# ATS.net
KiCad netlist of a schematic drawn in EAGLE
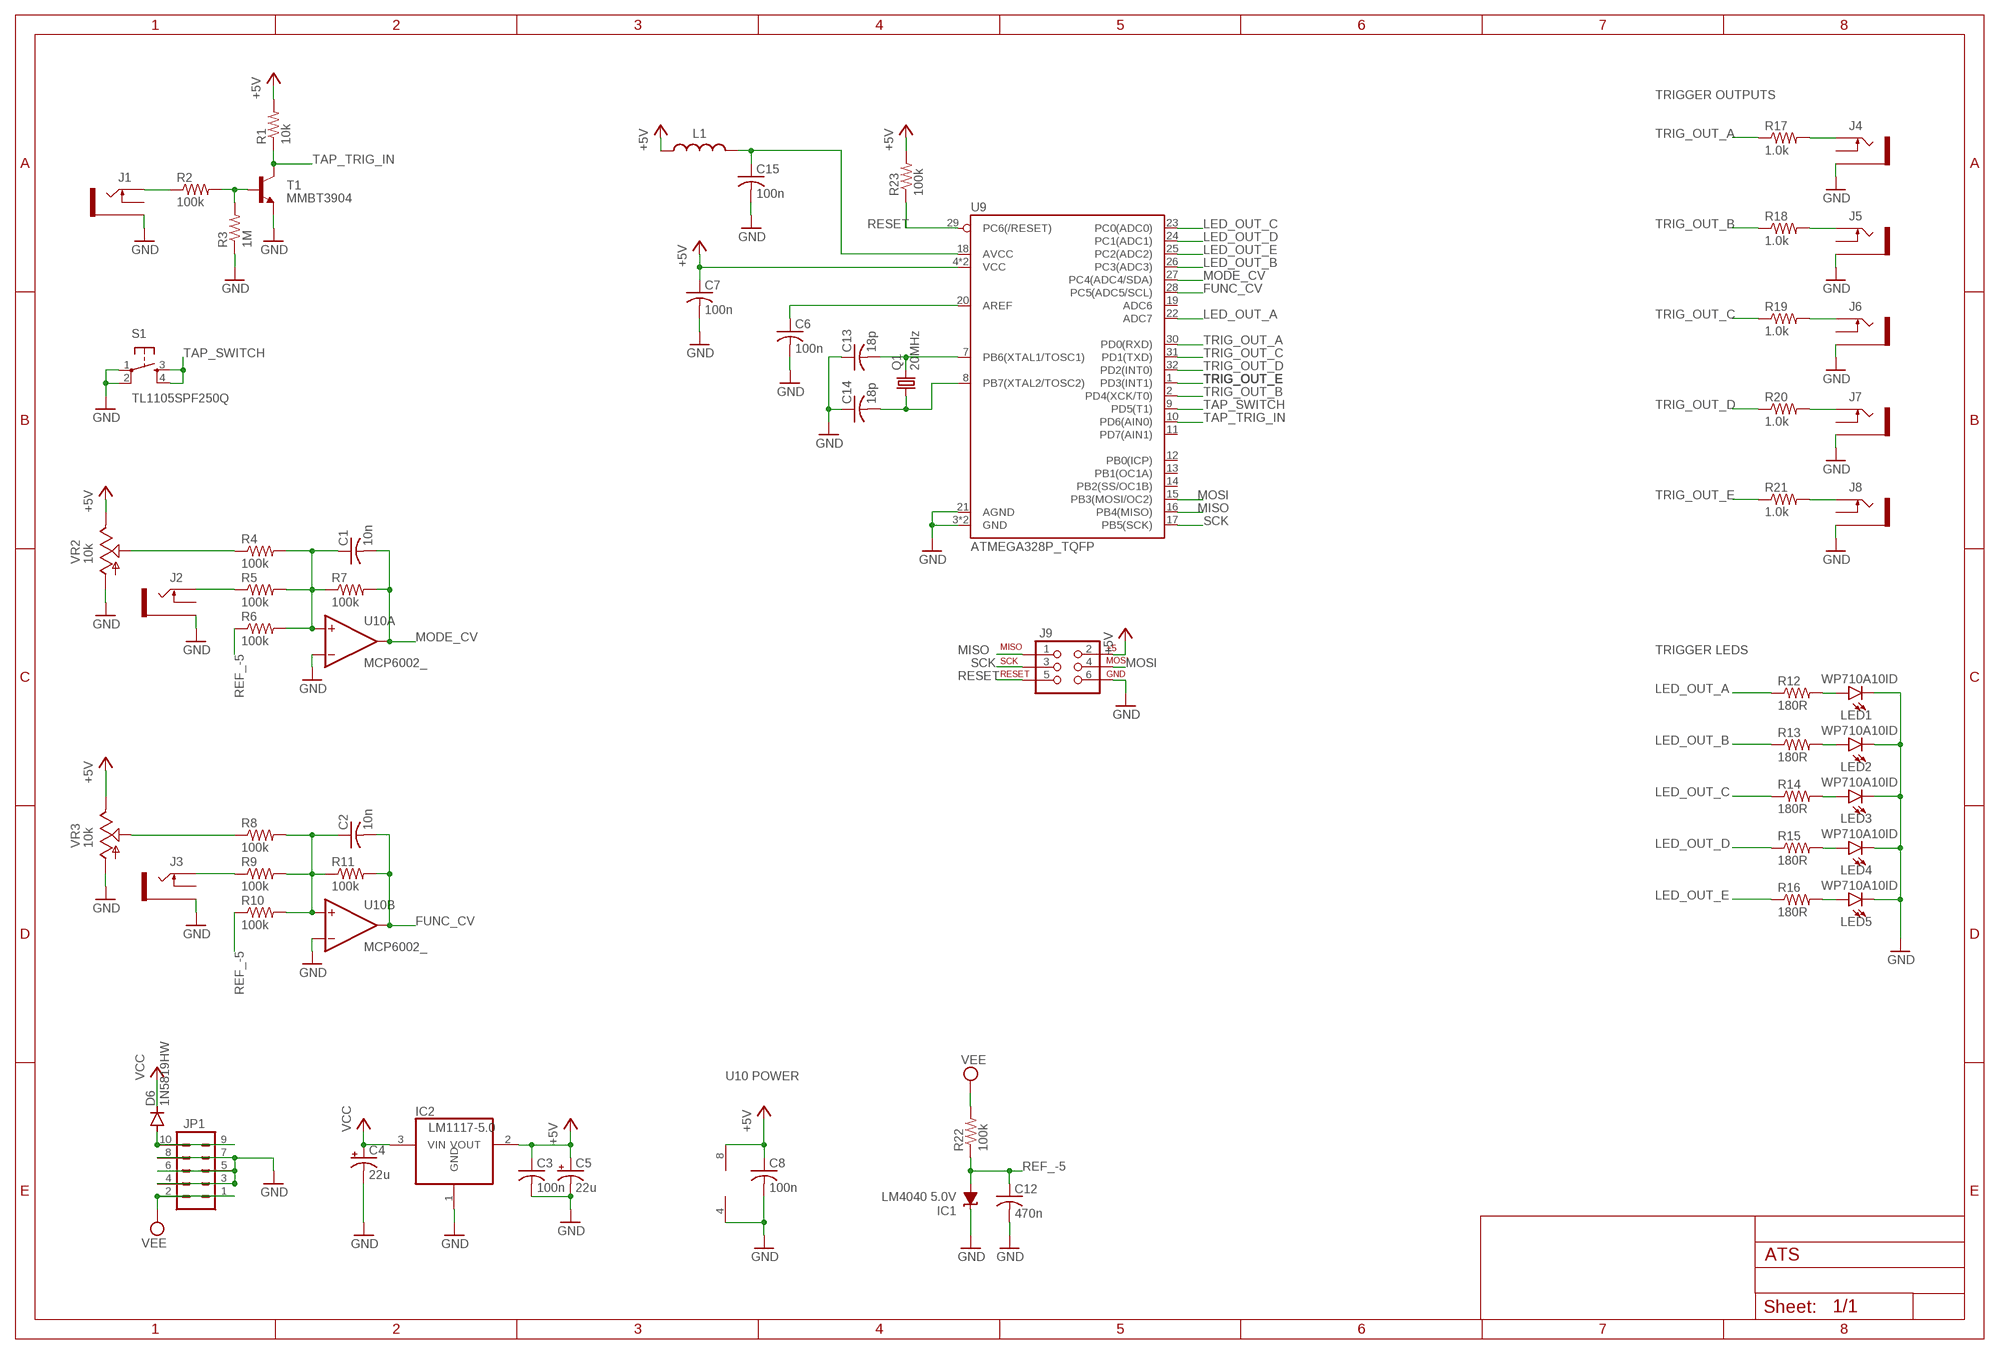
[diagram p0: schematic, sheet 1]

(export (version "E")
  (design (tool "Eeschema 10.0.6"))
  (components
    (comp (ref "C1")
      (value "10n")
      (footprint "eagle-import:C0603")
      (libsource (lib "eagle-import") (part "C-USC0603"))
    )
    (comp (ref "C2")
      (value "10n")
      (footprint "eagle-import:C0603")
      (libsource (lib "eagle-import") (part "C-USC0603"))
    )
    (comp (ref "C3")
      (value "100n")
      (footprint "eagle-import:C0603")
      (libsource (lib "eagle-import") (part "C-USC0603"))
    )
    (comp (ref "C4")
      (value "22u")
      (footprint "eagle-import:PANASONIC_C")
      (libsource (lib "eagle-import") (part "CPOL-USC"))
    )
    (comp (ref "C5")
      (value "22u")
      (footprint "eagle-import:PANASONIC_C")
      (libsource (lib "eagle-import") (part "CPOL-USC"))
    )
    (comp (ref "C6")
      (value "100n")
      (footprint "eagle-import:C0603")
      (libsource (lib "eagle-import") (part "C-USC0603"))
    )
    (comp (ref "C7")
      (value "100n")
      (footprint "eagle-import:C0603")
      (libsource (lib "eagle-import") (part "C-USC0603"))
    )
    (comp (ref "C8")
      (value "100n")
      (footprint "eagle-import:C0603")
      (libsource (lib "eagle-import") (part "C-USC0603"))
    )
    (comp (ref "C12")
      (value "470n")
      (footprint "eagle-import:C0603")
      (libsource (lib "eagle-import") (part "C-USC0603"))
    )
    (comp (ref "C13")
      (value "18p")
      (footprint "eagle-import:C0603")
      (libsource (lib "eagle-import") (part "C-USC0603"))
    )
    (comp (ref "C14")
      (value "18p")
      (footprint "eagle-import:C0603")
      (libsource (lib "eagle-import") (part "C-USC0603"))
    )
    (comp (ref "C15")
      (value "100n")
      (footprint "eagle-import:C0603")
      (libsource (lib "eagle-import") (part "C-USC0603"))
    )
    (comp (ref "D6")
      (value "1N5819HW")
      (footprint "eagle-import:SOD123")
      (libsource (lib "eagle-import") (part "DIODE-SOD123"))
    )
    (comp (ref "IC1")
      (value "LM4040 5.0V")
      (footprint "eagle-import:DBZ_R-PDSO-G3")
      (fields (field (name "MF") "TEXAS INSTRUMENT CONNECTORS") (field (name "MPN") "LM4041C12QDBZT"))
      (libsource (lib "eagle-import") (part "LM4041DBZC12"))
    )
    (comp (ref "IC2")
      (value "LM1117-5.0")
      (footprint "eagle-import:SOT223")
      (fields (field (name "MPN") "REG1117"))
      (libsource (lib "eagle-import") (part "REG1117"))
    )
    (comp (ref "J1")
      (value "THONKICONNNEW")
      (footprint "eagle-import:WQP-PJ301M-12_JACK")
      (libsource (lib "eagle-import") (part "THONKICONNNEW"))
    )
    (comp (ref "J2")
      (value "THONKICONNNEW")
      (footprint "eagle-import:WQP-PJ301M-12_JACK")
      (libsource (lib "eagle-import") (part "THONKICONNNEW"))
    )
    (comp (ref "J3")
      (value "THONKICONNNEW")
      (footprint "eagle-import:WQP-PJ301M-12_JACK")
      (libsource (lib "eagle-import") (part "THONKICONNNEW"))
    )
    (comp (ref "J4")
      (value "THONKICONNNEW")
      (footprint "eagle-import:WQP-PJ301M-12_JACK")
      (libsource (lib "eagle-import") (part "THONKICONNNEW"))
    )
    (comp (ref "J5")
      (value "THONKICONNNEW")
      (footprint "eagle-import:WQP-PJ301M-12_JACK")
      (libsource (lib "eagle-import") (part "THONKICONNNEW"))
    )
    (comp (ref "J6")
      (value "THONKICONNNEW")
      (footprint "eagle-import:WQP-PJ301M-12_JACK")
      (libsource (lib "eagle-import") (part "THONKICONNNEW"))
    )
    (comp (ref "J7")
      (value "THONKICONNNEW")
      (footprint "eagle-import:WQP-PJ301M-12_JACK")
      (libsource (lib "eagle-import") (part "THONKICONNNEW"))
    )
    (comp (ref "J8")
      (value "THONKICONNNEW")
      (footprint "eagle-import:WQP-PJ301M-12_JACK")
      (libsource (lib "eagle-import") (part "THONKICONNNEW"))
    )
    (comp (ref "J9")
      (value "AVR_SPI_PRG_6PTH")
      (footprint "eagle-import:2X3")
      (libsource (lib "eagle-import") (part "AVR_SPI_PRG_6PTH"))
    )
    (comp (ref "JP1")
      (value "EURO_POWER_HEADERREGULAR")
      (footprint "eagle-import:EURO_POWER_HEADER")
      (libsource (lib "eagle-import") (part "EURO_POWER_HEADERREGULAR"))
    )
    (comp (ref "L1")
      (value "470Ohm@100MHz")
      (footprint "eagle-import:WE-CBF_0603(W=2.2)")
      (libsource (lib "eagle-import") (part "WE-CBF_0603_WB_HS_742792642"))
    )
    (comp (ref "LED1")
      (value "WP710A10ID")
      (footprint "eagle-import:LED_3MM")
      (fields (field (name "SPICEPREFIX") "D"))
      (libsource (lib "eagle-import") (part "LED3MM"))
    )
    (comp (ref "LED2")
      (value "WP710A10ID")
      (footprint "eagle-import:LED_3MM")
      (libsource (lib "eagle-import") (part "LED3MM"))
    )
    (comp (ref "LED3")
      (value "WP710A10ID")
      (footprint "eagle-import:LED_3MM")
      (libsource (lib "eagle-import") (part "LED3MM"))
    )
    (comp (ref "LED4")
      (value "WP710A10ID")
      (footprint "eagle-import:LED_3MM")
      (libsource (lib "eagle-import") (part "LED3MM"))
    )
    (comp (ref "LED5")
      (value "WP710A10ID")
      (footprint "eagle-import:LED_3MM")
      (libsource (lib "eagle-import") (part "LED3MM"))
    )
    (comp (ref "Q1")
      (value "20MHz")
      (footprint "eagle-import:HC49UP")
      (libsource (lib "eagle-import") (part "CRYSTALHC49UP"))
    )
    (comp (ref "R1")
      (value "10k")
      (footprint "eagle-import:R0603")
      (libsource (lib "eagle-import") (part "R-US_R0603"))
    )
    (comp (ref "R2")
      (value "100k")
      (footprint "eagle-import:R0603")
      (libsource (lib "eagle-import") (part "R-US_R0603"))
    )
    (comp (ref "R3")
      (value "1M")
      (footprint "eagle-import:R0603")
      (libsource (lib "eagle-import") (part "R-US_R0603"))
    )
    (comp (ref "R4")
      (value "100k")
      (footprint "eagle-import:R0603")
      (libsource (lib "eagle-import") (part "R-US_R0603"))
    )
    (comp (ref "R5")
      (value "100k")
      (footprint "eagle-import:R0603")
      (libsource (lib "eagle-import") (part "R-US_R0603"))
    )
    (comp (ref "R6")
      (value "100k")
      (footprint "eagle-import:R0603")
      (libsource (lib "eagle-import") (part "R-US_R0603"))
    )
    (comp (ref "R7")
      (value "100k")
      (footprint "eagle-import:R0603")
      (libsource (lib "eagle-import") (part "R-US_R0603"))
    )
    (comp (ref "R8")
      (value "100k")
      (footprint "eagle-import:R0603")
      (libsource (lib "eagle-import") (part "R-US_R0603"))
    )
    (comp (ref "R9")
      (value "100k")
      (footprint "eagle-import:R0603")
      (libsource (lib "eagle-import") (part "R-US_R0603"))
    )
    (comp (ref "R10")
      (value "100k")
      (footprint "eagle-import:R0603")
      (libsource (lib "eagle-import") (part "R-US_R0603"))
    )
    (comp (ref "R11")
      (value "100k")
      (footprint "eagle-import:R0603")
      (libsource (lib "eagle-import") (part "R-US_R0603"))
    )
    (comp (ref "R12")
      (value "180R")
      (footprint "eagle-import:R0603")
      (libsource (lib "eagle-import") (part "R-US_R0603"))
    )
    (comp (ref "R13")
      (value "180R")
      (footprint "eagle-import:R0603")
      (libsource (lib "eagle-import") (part "R-US_R0603"))
    )
    (comp (ref "R14")
      (value "180R")
      (footprint "eagle-import:R0603")
      (libsource (lib "eagle-import") (part "R-US_R0603"))
    )
    (comp (ref "R15")
      (value "180R")
      (footprint "eagle-import:R0603")
      (libsource (lib "eagle-import") (part "R-US_R0603"))
    )
    (comp (ref "R16")
      (value "180R")
      (footprint "eagle-import:R0603")
      (libsource (lib "eagle-import") (part "R-US_R0603"))
    )
    (comp (ref "R17")
      (value "1.0k")
      (footprint "eagle-import:R0603")
      (libsource (lib "eagle-import") (part "R-US_R0603"))
    )
    (comp (ref "R18")
      (value "1.0k")
      (footprint "eagle-import:R0603")
      (libsource (lib "eagle-import") (part "R-US_R0603"))
    )
    (comp (ref "R19")
      (value "1.0k")
      (footprint "eagle-import:R0603")
      (libsource (lib "eagle-import") (part "R-US_R0603"))
    )
    (comp (ref "R20")
      (value "1.0k")
      (footprint "eagle-import:R0603")
      (libsource (lib "eagle-import") (part "R-US_R0603"))
    )
    (comp (ref "R21")
      (value "1.0k")
      (footprint "eagle-import:R0603")
      (libsource (lib "eagle-import") (part "R-US_R0603"))
    )
    (comp (ref "R22")
      (value "100k")
      (footprint "eagle-import:R0603")
      (libsource (lib "eagle-import") (part "R-US_R0603"))
    )
    (comp (ref "R23")
      (value "100k")
      (footprint "eagle-import:R0603")
      (libsource (lib "eagle-import") (part "R-US_R0603"))
    )
    (comp (ref "S1")
      (value "TL1105SPF250Q")
      (footprint "eagle-import:TACTILE-PTH")
      (libsource (lib "eagle-import") (part "TAC_SWITCHPTH"))
    )
    (comp (ref "T1")
      (value "MMBT3904")
      (footprint "eagle-import:SOT23-BEC")
      (libsource (lib "eagle-import") (part "-NPN-SOT23-BECMMBT3904LT1"))
    )
    (comp (ref "U9")
      (value "ATMEGA328P_TQFP")
      (footprint "eagle-import:TQFP32-08")
      (libsource (lib "eagle-import") (part "ATMEGA328P_TQFP"))
    )
    (comp (ref "U10")
      (value "MCP6002_")
      (footprint "eagle-import:SO08")
      (libsource (lib "eagle-import") (part "MCP6002_"))
    )
    (comp (ref "VR2")
      (value "10k")
      (footprint "eagle-import:9MM_SNAP-IN_POT")
      (libsource (lib "eagle-import") (part "9MM_SNAP-IN_POT_"))
    )
    (comp (ref "VR3")
      (value "10k")
      (footprint "eagle-import:9MM_SNAP-IN_POT")
      (libsource (lib "eagle-import") (part "9MM_SNAP-IN_POT_"))
    )
  )
  (nets
    (net (code "1") (name "+5V") (class "Default")
      (node (ref "C3") (pin "1") (pinfunction "1_1") (pintype "passive"))
      (node (ref "C5") (pin "+") (pinfunction "+_+") (pintype "passive"))
      (node (ref "C7") (pin "1") (pinfunction "1_1") (pintype "passive"))
      (node (ref "C8") (pin "1") (pinfunction "1_1") (pintype "passive"))
      (node (ref "IC2") (pin "2") (pinfunction "VOUT_2") (pintype "output"))
      (node (ref "J9") (pin "2") (pinfunction "2_2") (pintype "passive"))
      (node (ref "L1") (pin "1") (pinfunction "1_1") (pintype "passive"))
      (node (ref "R1") (pin "2") (pinfunction "2_2") (pintype "passive"))
      (node (ref "R23") (pin "2") (pinfunction "2_2") (pintype "passive"))
      (node (ref "U10") (pin "8") (pinfunction "V+_8") (pintype "power_in"))
      (node (ref "U9") (pin "4") (pinfunction "VCC_4") (pintype "bidirectional"))
      (node (ref "U9") (pin "6") (pinfunction "VCC_6") (pintype "bidirectional"))
      (node (ref "VR2") (pin "3") (pinfunction "E_3") (pintype "passive"))
      (node (ref "VR3") (pin "3") (pinfunction "E_3") (pintype "passive"))
    )
    (net (code "2") (name "/FUNC_CV") (class "Default")
      (node (ref "C2") (pin "2") (pinfunction "2_2") (pintype "passive"))
      (node (ref "R11") (pin "2") (pinfunction "2_2") (pintype "passive"))
      (node (ref "U10") (pin "7") (pinfunction "OUT_7") (pintype "output"))
      (node (ref "U9") (pin "28") (pinfunction "PC5(ADC5/SCL)_28") (pintype "bidirectional"))
    )
    (net (code "3") (name "/LED_OUT_A") (class "Default")
      (node (ref "R12") (pin "1") (pinfunction "1_1") (pintype "passive"))
      (node (ref "U9") (pin "22") (pinfunction "ADC7_22") (pintype "bidirectional"))
    )
    (net (code "4") (name "/LED_OUT_B") (class "Default")
      (node (ref "R13") (pin "1") (pinfunction "1_1") (pintype "passive"))
      (node (ref "U9") (pin "26") (pinfunction "PC3(ADC3)_26") (pintype "bidirectional"))
    )
    (net (code "5") (name "/LED_OUT_C") (class "Default")
      (node (ref "R14") (pin "1") (pinfunction "1_1") (pintype "passive"))
      (node (ref "U9") (pin "23") (pinfunction "PC0(ADC0)_23") (pintype "bidirectional"))
    )
    (net (code "6") (name "/LED_OUT_D") (class "Default")
      (node (ref "R15") (pin "1") (pinfunction "1_1") (pintype "passive"))
      (node (ref "U9") (pin "24") (pinfunction "PC1(ADC1)_24") (pintype "bidirectional"))
    )
    (net (code "7") (name "/LED_OUT_E") (class "Default")
      (node (ref "R16") (pin "1") (pinfunction "1_1") (pintype "passive"))
      (node (ref "U9") (pin "25") (pinfunction "PC2(ADC2)_25") (pintype "bidirectional"))
    )
    (net (code "8") (name "/MISO") (class "Default")
      (node (ref "J9") (pin "1") (pinfunction "1_1") (pintype "passive"))
      (node (ref "U9") (pin "16") (pinfunction "PB4(MISO)_16") (pintype "bidirectional"))
    )
    (net (code "9") (name "/MODE_CV") (class "Default")
      (node (ref "C1") (pin "2") (pinfunction "2_2") (pintype "passive"))
      (node (ref "R7") (pin "2") (pinfunction "2_2") (pintype "passive"))
      (node (ref "U10") (pin "1") (pinfunction "OUT_1") (pintype "output"))
      (node (ref "U9") (pin "27") (pinfunction "PC4(ADC4/SDA)_27") (pintype "bidirectional"))
    )
    (net (code "10") (name "/MOSI") (class "Default")
      (node (ref "J9") (pin "4") (pinfunction "4_4") (pintype "passive"))
      (node (ref "U9") (pin "15") (pinfunction "PB3(MOSI/OC2)_15") (pintype "bidirectional"))
    )
    (net (code "11") (name "/REF_-5") (class "Default")
      (node (ref "C12") (pin "1") (pinfunction "1_1") (pintype "passive"))
      (node (ref "IC1") (pin "2") (pinfunction "A_2") (pintype "passive"))
      (node (ref "R10") (pin "1") (pinfunction "1_1") (pintype "passive"))
      (node (ref "R22") (pin "1") (pinfunction "1_1") (pintype "passive"))
      (node (ref "R6") (pin "1") (pinfunction "1_1") (pintype "passive"))
    )
    (net (code "12") (name "/RESET") (class "Default")
      (node (ref "J9") (pin "5") (pinfunction "5_5") (pintype "passive"))
      (node (ref "R23") (pin "1") (pinfunction "1_1") (pintype "passive"))
      (node (ref "U9") (pin "29") (pinfunction "PC6(/RESET)_29") (pintype "bidirectional"))
    )
    (net (code "13") (name "/SCK") (class "Default")
      (node (ref "J9") (pin "3") (pinfunction "3_3") (pintype "passive"))
      (node (ref "U9") (pin "17") (pinfunction "PB5(SCK)_17") (pintype "bidirectional"))
    )
    (net (code "14") (name "/TAP_SWITCH") (class "Default")
      (node (ref "S1") (pin "3") (pinfunction "3_3") (pintype "passive"))
      (node (ref "S1") (pin "4") (pinfunction "4_4") (pintype "passive"))
      (node (ref "U9") (pin "9") (pinfunction "PD5(T1)_9") (pintype "bidirectional"))
    )
    (net (code "15") (name "/TAP_TRIG_IN") (class "Default")
      (node (ref "R1") (pin "1") (pinfunction "1_1") (pintype "passive"))
      (node (ref "T1") (pin "C") (pinfunction "C_C") (pintype "passive"))
      (node (ref "U9") (pin "10") (pinfunction "PD6(AIN0)_10") (pintype "bidirectional"))
    )
    (net (code "16") (name "/TRIG_OUT_A") (class "Default")
      (node (ref "R17") (pin "1") (pinfunction "1_1") (pintype "passive"))
      (node (ref "U9") (pin "30") (pinfunction "PD0(RXD)_30") (pintype "bidirectional"))
    )
    (net (code "17") (name "/TRIG_OUT_B") (class "Default")
      (node (ref "R18") (pin "1") (pinfunction "1_1") (pintype "passive"))
      (node (ref "U9") (pin "2") (pinfunction "PD4(XCK/T0)_2") (pintype "bidirectional"))
    )
    (net (code "18") (name "/TRIG_OUT_C") (class "Default")
      (node (ref "R19") (pin "1") (pinfunction "1_1") (pintype "passive"))
      (node (ref "U9") (pin "31") (pinfunction "PD1(TXD)_31") (pintype "bidirectional"))
    )
    (net (code "19") (name "/TRIG_OUT_D") (class "Default")
      (node (ref "R20") (pin "1") (pinfunction "1_1") (pintype "passive"))
      (node (ref "U9") (pin "32") (pinfunction "PD2(INT0)_32") (pintype "bidirectional"))
    )
    (net (code "20") (name "/TRIG_OUT_E") (class "Default")
      (node (ref "R21") (pin "1") (pinfunction "1_1") (pintype "passive"))
      (node (ref "U9") (pin "1") (pinfunction "PD3(INT1)_1") (pintype "bidirectional"))
    )
    (net (code "21") (name "GND") (class "Default")
      (node (ref "C12") (pin "2") (pinfunction "2_2") (pintype "passive"))
      (node (ref "C13") (pin "1") (pinfunction "1_1") (pintype "passive"))
      (node (ref "C14") (pin "1") (pinfunction "1_1") (pintype "passive"))
      (node (ref "C15") (pin "2") (pinfunction "2_2") (pintype "passive"))
      (node (ref "C3") (pin "2") (pinfunction "2_2") (pintype "passive"))
      (node (ref "C4") (pin "-") (pinfunction "-_-") (pintype "passive"))
      (node (ref "C5") (pin "-") (pinfunction "-_-") (pintype "passive"))
      (node (ref "C6") (pin "2") (pinfunction "2_2") (pintype "passive"))
      (node (ref "C7") (pin "2") (pinfunction "2_2") (pintype "passive"))
      (node (ref "C8") (pin "2") (pinfunction "2_2") (pintype "passive"))
      (node (ref "IC1") (pin "1") (pinfunction "C_1") (pintype "passive"))
      (node (ref "IC2") (pin "1") (pinfunction "GND_1") (pintype "power_in"))
      (node (ref "J1") (pin "P$3_SLEEVE") (pinfunction "SLEEVE_P$3_SLEEVE") (pintype "passive"))
      (node (ref "J2") (pin "P$3_SLEEVE") (pinfunction "SLEEVE_P$3_SLEEVE") (pintype "passive"))
      (node (ref "J3") (pin "P$3_SLEEVE") (pinfunction "SLEEVE_P$3_SLEEVE") (pintype "passive"))
      (node (ref "J4") (pin "P$3_SLEEVE") (pinfunction "SLEEVE_P$3_SLEEVE") (pintype "passive"))
      (node (ref "J5") (pin "P$3_SLEEVE") (pinfunction "SLEEVE_P$3_SLEEVE") (pintype "passive"))
      (node (ref "J6") (pin "P$3_SLEEVE") (pinfunction "SLEEVE_P$3_SLEEVE") (pintype "passive"))
      (node (ref "J7") (pin "P$3_SLEEVE") (pinfunction "SLEEVE_P$3_SLEEVE") (pintype "passive"))
      (node (ref "J8") (pin "P$3_SLEEVE") (pinfunction "SLEEVE_P$3_SLEEVE") (pintype "passive"))
      (node (ref "J9") (pin "6") (pinfunction "6_6") (pintype "passive"))
      (node (ref "JP1") (pin "3") (pinfunction "3_3") (pintype "passive"))
      (node (ref "JP1") (pin "4") (pinfunction "4_4") (pintype "passive"))
      (node (ref "JP1") (pin "5") (pinfunction "5_5") (pintype "passive"))
      (node (ref "JP1") (pin "6") (pinfunction "6_6") (pintype "passive"))
      (node (ref "JP1") (pin "7") (pinfunction "7_7") (pintype "passive"))
      (node (ref "JP1") (pin "8") (pinfunction "8_8") (pintype "passive"))
      (node (ref "LED1") (pin "K") (pinfunction "C_K") (pintype "passive"))
      (node (ref "LED2") (pin "K") (pinfunction "C_K") (pintype "passive"))
      (node (ref "LED3") (pin "K") (pinfunction "C_K") (pintype "passive"))
      (node (ref "LED4") (pin "K") (pinfunction "C_K") (pintype "passive"))
      (node (ref "LED5") (pin "K") (pinfunction "C_K") (pintype "passive"))
      (node (ref "R3") (pin "1") (pinfunction "1_1") (pintype "passive"))
      (node (ref "S1") (pin "1") (pinfunction "1_1") (pintype "passive"))
      (node (ref "S1") (pin "2") (pinfunction "2_2") (pintype "passive"))
      (node (ref "T1") (pin "E") (pinfunction "E_E") (pintype "passive"))
      (node (ref "U10") (pin "2") (pinfunction "-IN_2") (pintype "input"))
      (node (ref "U10") (pin "4") (pinfunction "V-_4") (pintype "power_in"))
      (node (ref "U10") (pin "6") (pinfunction "-IN_6") (pintype "input"))
      (node (ref "U9") (pin "21") (pinfunction "AGND_21") (pintype "bidirectional"))
      (node (ref "U9") (pin "3") (pinfunction "GND_3") (pintype "bidirectional"))
      (node (ref "U9") (pin "5") (pinfunction "GND_5") (pintype "bidirectional"))
      (node (ref "VR2") (pin "1") (pinfunction "A_1") (pintype "passive"))
      (node (ref "VR3") (pin "1") (pinfunction "A_1") (pintype "passive"))
    )
    (net (code "22") (name "Net-(D6-PadA)") (class "Default")
      (node (ref "D6") (pin "A") (pinfunction "A_A") (pintype "passive"))
      (node (ref "JP1") (pin "10") (pinfunction "10_10") (pintype "passive"))
      (node (ref "JP1") (pin "9") (pinfunction "9_9") (pintype "passive"))
    )
    (net (code "23") (name "Net-(J1-TIP)") (class "Default")
      (node (ref "J1") (pin "P$1_TIP") (pinfunction "TIP_P$1_TIP") (pintype "passive"))
      (node (ref "R2") (pin "1") (pinfunction "1_1") (pintype "passive"))
    )
    (net (code "24") (name "Net-(J2-TIP)") (class "Default")
      (node (ref "J2") (pin "P$1_TIP") (pinfunction "TIP_P$1_TIP") (pintype "passive"))
      (node (ref "R5") (pin "1") (pinfunction "1_1") (pintype "passive"))
    )
    (net (code "25") (name "Net-(J3-TIP)") (class "Default")
      (node (ref "J3") (pin "P$1_TIP") (pinfunction "TIP_P$1_TIP") (pintype "passive"))
      (node (ref "R9") (pin "1") (pinfunction "1_1") (pintype "passive"))
    )
    (net (code "26") (name "Net-(J4-TIP)") (class "Default")
      (node (ref "J4") (pin "P$1_TIP") (pinfunction "TIP_P$1_TIP") (pintype "passive"))
      (node (ref "R17") (pin "2") (pinfunction "2_2") (pintype "passive"))
    )
    (net (code "27") (name "Net-(J5-TIP)") (class "Default")
      (node (ref "J5") (pin "P$1_TIP") (pinfunction "TIP_P$1_TIP") (pintype "passive"))
      (node (ref "R18") (pin "2") (pinfunction "2_2") (pintype "passive"))
    )
    (net (code "28") (name "Net-(J6-TIP)") (class "Default")
      (node (ref "J6") (pin "P$1_TIP") (pinfunction "TIP_P$1_TIP") (pintype "passive"))
      (node (ref "R19") (pin "2") (pinfunction "2_2") (pintype "passive"))
    )
    (net (code "29") (name "Net-(J7-TIP)") (class "Default")
      (node (ref "J7") (pin "P$1_TIP") (pinfunction "TIP_P$1_TIP") (pintype "passive"))
      (node (ref "R20") (pin "2") (pinfunction "2_2") (pintype "passive"))
    )
    (net (code "30") (name "Net-(J8-TIP)") (class "Default")
      (node (ref "J8") (pin "P$1_TIP") (pinfunction "TIP_P$1_TIP") (pintype "passive"))
      (node (ref "R21") (pin "2") (pinfunction "2_2") (pintype "passive"))
    )
    (net (code "31") (name "Net-(LED1-PadA)") (class "Default")
      (node (ref "LED1") (pin "A") (pinfunction "A_A") (pintype "passive"))
      (node (ref "R12") (pin "2") (pinfunction "2_2") (pintype "passive"))
    )
    (net (code "32") (name "Net-(LED2-PadA)") (class "Default")
      (node (ref "LED2") (pin "A") (pinfunction "A_A") (pintype "passive"))
      (node (ref "R13") (pin "2") (pinfunction "2_2") (pintype "passive"))
    )
    (net (code "33") (name "Net-(LED3-PadA)") (class "Default")
      (node (ref "LED3") (pin "A") (pinfunction "A_A") (pintype "passive"))
      (node (ref "R14") (pin "2") (pinfunction "2_2") (pintype "passive"))
    )
    (net (code "34") (name "Net-(LED4-PadA)") (class "Default")
      (node (ref "LED4") (pin "A") (pinfunction "A_A") (pintype "passive"))
      (node (ref "R15") (pin "2") (pinfunction "2_2") (pintype "passive"))
    )
    (net (code "35") (name "Net-(LED5-PadA)") (class "Default")
      (node (ref "LED5") (pin "A") (pinfunction "A_A") (pintype "passive"))
      (node (ref "R16") (pin "2") (pinfunction "2_2") (pintype "passive"))
    )
    (net (code "36") (name "Net-(R2-Pad2)") (class "Default")
      (node (ref "R2") (pin "2") (pinfunction "2_2") (pintype "passive"))
      (node (ref "R3") (pin "2") (pinfunction "2_2") (pintype "passive"))
      (node (ref "T1") (pin "B") (pinfunction "B_B") (pintype "passive"))
    )
    (net (code "37") (name "Net-(U9-AREF)") (class "Default")
      (node (ref "C6") (pin "1") (pinfunction "1_1") (pintype "passive"))
      (node (ref "U9") (pin "20") (pinfunction "AREF_20") (pintype "bidirectional"))
    )
    (net (code "38") (name "Net-(U9-AVCC)") (class "Default")
      (node (ref "C15") (pin "1") (pinfunction "1_1") (pintype "passive"))
      (node (ref "L1") (pin "2") (pinfunction "2_2") (pintype "passive"))
      (node (ref "U9") (pin "18") (pinfunction "AVCC_18") (pintype "bidirectional"))
    )
    (net (code "39") (name "Net-(U9-PB6(XTAL1{slash}TOSC1))") (class "Default")
      (node (ref "C13") (pin "2") (pinfunction "2_2") (pintype "passive"))
      (node (ref "Q1") (pin "2") (pinfunction "2_2") (pintype "passive"))
      (node (ref "U9") (pin "7") (pinfunction "PB6(XTAL1/TOSC1)_7") (pintype "bidirectional"))
    )
    (net (code "40") (name "Net-(U9-PB7(XTAL2{slash}TOSC2))") (class "Default")
      (node (ref "C14") (pin "2") (pinfunction "2_2") (pintype "passive"))
      (node (ref "Q1") (pin "1") (pinfunction "1_1") (pintype "passive"))
      (node (ref "U9") (pin "8") (pinfunction "PB7(XTAL2/TOSC2)_8") (pintype "bidirectional"))
    )
    (net (code "41") (name "Net-(U10A-+IN)") (class "Default")
      (node (ref "C1") (pin "1") (pinfunction "1_1") (pintype "passive"))
      (node (ref "R4") (pin "2") (pinfunction "2_2") (pintype "passive"))
      (node (ref "R5") (pin "2") (pinfunction "2_2") (pintype "passive"))
      (node (ref "R6") (pin "2") (pinfunction "2_2") (pintype "passive"))
      (node (ref "R7") (pin "1") (pinfunction "1_1") (pintype "passive"))
      (node (ref "U10") (pin "3") (pinfunction "+IN_3") (pintype "input"))
    )
    (net (code "42") (name "Net-(U10B-+IN)") (class "Default")
      (node (ref "C2") (pin "1") (pinfunction "1_1") (pintype "passive"))
      (node (ref "R10") (pin "2") (pinfunction "2_2") (pintype "passive"))
      (node (ref "R11") (pin "1") (pinfunction "1_1") (pintype "passive"))
      (node (ref "R8") (pin "2") (pinfunction "2_2") (pintype "passive"))
      (node (ref "R9") (pin "2") (pinfunction "2_2") (pintype "passive"))
      (node (ref "U10") (pin "5") (pinfunction "+IN_5") (pintype "input"))
    )
    (net (code "43") (name "Net-(VR2-S)") (class "Default")
      (node (ref "R4") (pin "1") (pinfunction "1_1") (pintype "passive"))
      (node (ref "VR2") (pin "2") (pinfunction "S_2") (pintype "passive"))
    )
    (net (code "44") (name "Net-(VR3-S)") (class "Default")
      (node (ref "R8") (pin "1") (pinfunction "1_1") (pintype "passive"))
      (node (ref "VR3") (pin "2") (pinfunction "S_2") (pintype "passive"))
    )
    (net (code "45") (name "VCC") (class "Default")
      (node (ref "C4") (pin "+") (pinfunction "+_+") (pintype "passive"))
      (node (ref "D6") (pin "C") (pinfunction "C_C") (pintype "passive"))
      (node (ref "IC2") (pin "3") (pinfunction "VIN_3") (pintype "input"))
    )
    (net (code "46") (name "VEE") (class "Default")
      (node (ref "JP1") (pin "1") (pinfunction "1_1") (pintype "passive"))
      (node (ref "JP1") (pin "2") (pinfunction "2_2") (pintype "passive"))
      (node (ref "R22") (pin "2") (pinfunction "2_2") (pintype "passive"))
    )
    (net (code "47") (name "unconnected-(J1-SWITCH-PadP$2_SWITCH)") (class "Default")
      (node (ref "J1") (pin "P$2_SWITCH") (pinfunction "SWITCH_P$2_SWITCH") (pintype "passive"))
    )
    (net (code "48") (name "unconnected-(J2-SWITCH-PadP$2_SWITCH)") (class "Default")
      (node (ref "J2") (pin "P$2_SWITCH") (pinfunction "SWITCH_P$2_SWITCH") (pintype "passive"))
    )
    (net (code "49") (name "unconnected-(J3-SWITCH-PadP$2_SWITCH)") (class "Default")
      (node (ref "J3") (pin "P$2_SWITCH") (pinfunction "SWITCH_P$2_SWITCH") (pintype "passive"))
    )
    (net (code "50") (name "unconnected-(J4-SWITCH-PadP$2_SWITCH)") (class "Default")
      (node (ref "J4") (pin "P$2_SWITCH") (pinfunction "SWITCH_P$2_SWITCH") (pintype "passive"))
    )
    (net (code "51") (name "unconnected-(J5-SWITCH-PadP$2_SWITCH)") (class "Default")
      (node (ref "J5") (pin "P$2_SWITCH") (pinfunction "SWITCH_P$2_SWITCH") (pintype "passive"))
    )
    (net (code "52") (name "unconnected-(J6-SWITCH-PadP$2_SWITCH)") (class "Default")
      (node (ref "J6") (pin "P$2_SWITCH") (pinfunction "SWITCH_P$2_SWITCH") (pintype "passive"))
    )
    (net (code "53") (name "unconnected-(J7-SWITCH-PadP$2_SWITCH)") (class "Default")
      (node (ref "J7") (pin "P$2_SWITCH") (pinfunction "SWITCH_P$2_SWITCH") (pintype "passive"))
    )
    (net (code "54") (name "unconnected-(J8-SWITCH-PadP$2_SWITCH)") (class "Default")
      (node (ref "J8") (pin "P$2_SWITCH") (pinfunction "SWITCH_P$2_SWITCH") (pintype "passive"))
    )
    (net (code "55") (name "unconnected-(U9-ADC6-Pad19)") (class "Default")
      (node (ref "U9") (pin "19") (pinfunction "ADC6_19") (pintype "bidirectional"))
    )
    (net (code "56") (name "unconnected-(U9-PB0(ICP)-Pad12)") (class "Default")
      (node (ref "U9") (pin "12") (pinfunction "PB0(ICP)_12") (pintype "bidirectional"))
    )
    (net (code "57") (name "unconnected-(U9-PB1(OC1A)-Pad13)") (class "Default")
      (node (ref "U9") (pin "13") (pinfunction "PB1(OC1A)_13") (pintype "bidirectional"))
    )
    (net (code "58") (name "unconnected-(U9-PB2(SS{slash}OC1B)-Pad14)") (class "Default")
      (node (ref "U9") (pin "14") (pinfunction "PB2(SS/OC1B)_14") (pintype "bidirectional"))
    )
    (net (code "59") (name "unconnected-(U9-PD7(AIN1)-Pad11)") (class "Default")
      (node (ref "U9") (pin "11") (pinfunction "PD7(AIN1)_11") (pintype "bidirectional"))
    )
  )
)
